# HVIB_v2.net
KiCad netlist of a schematic drawn in EAGLE
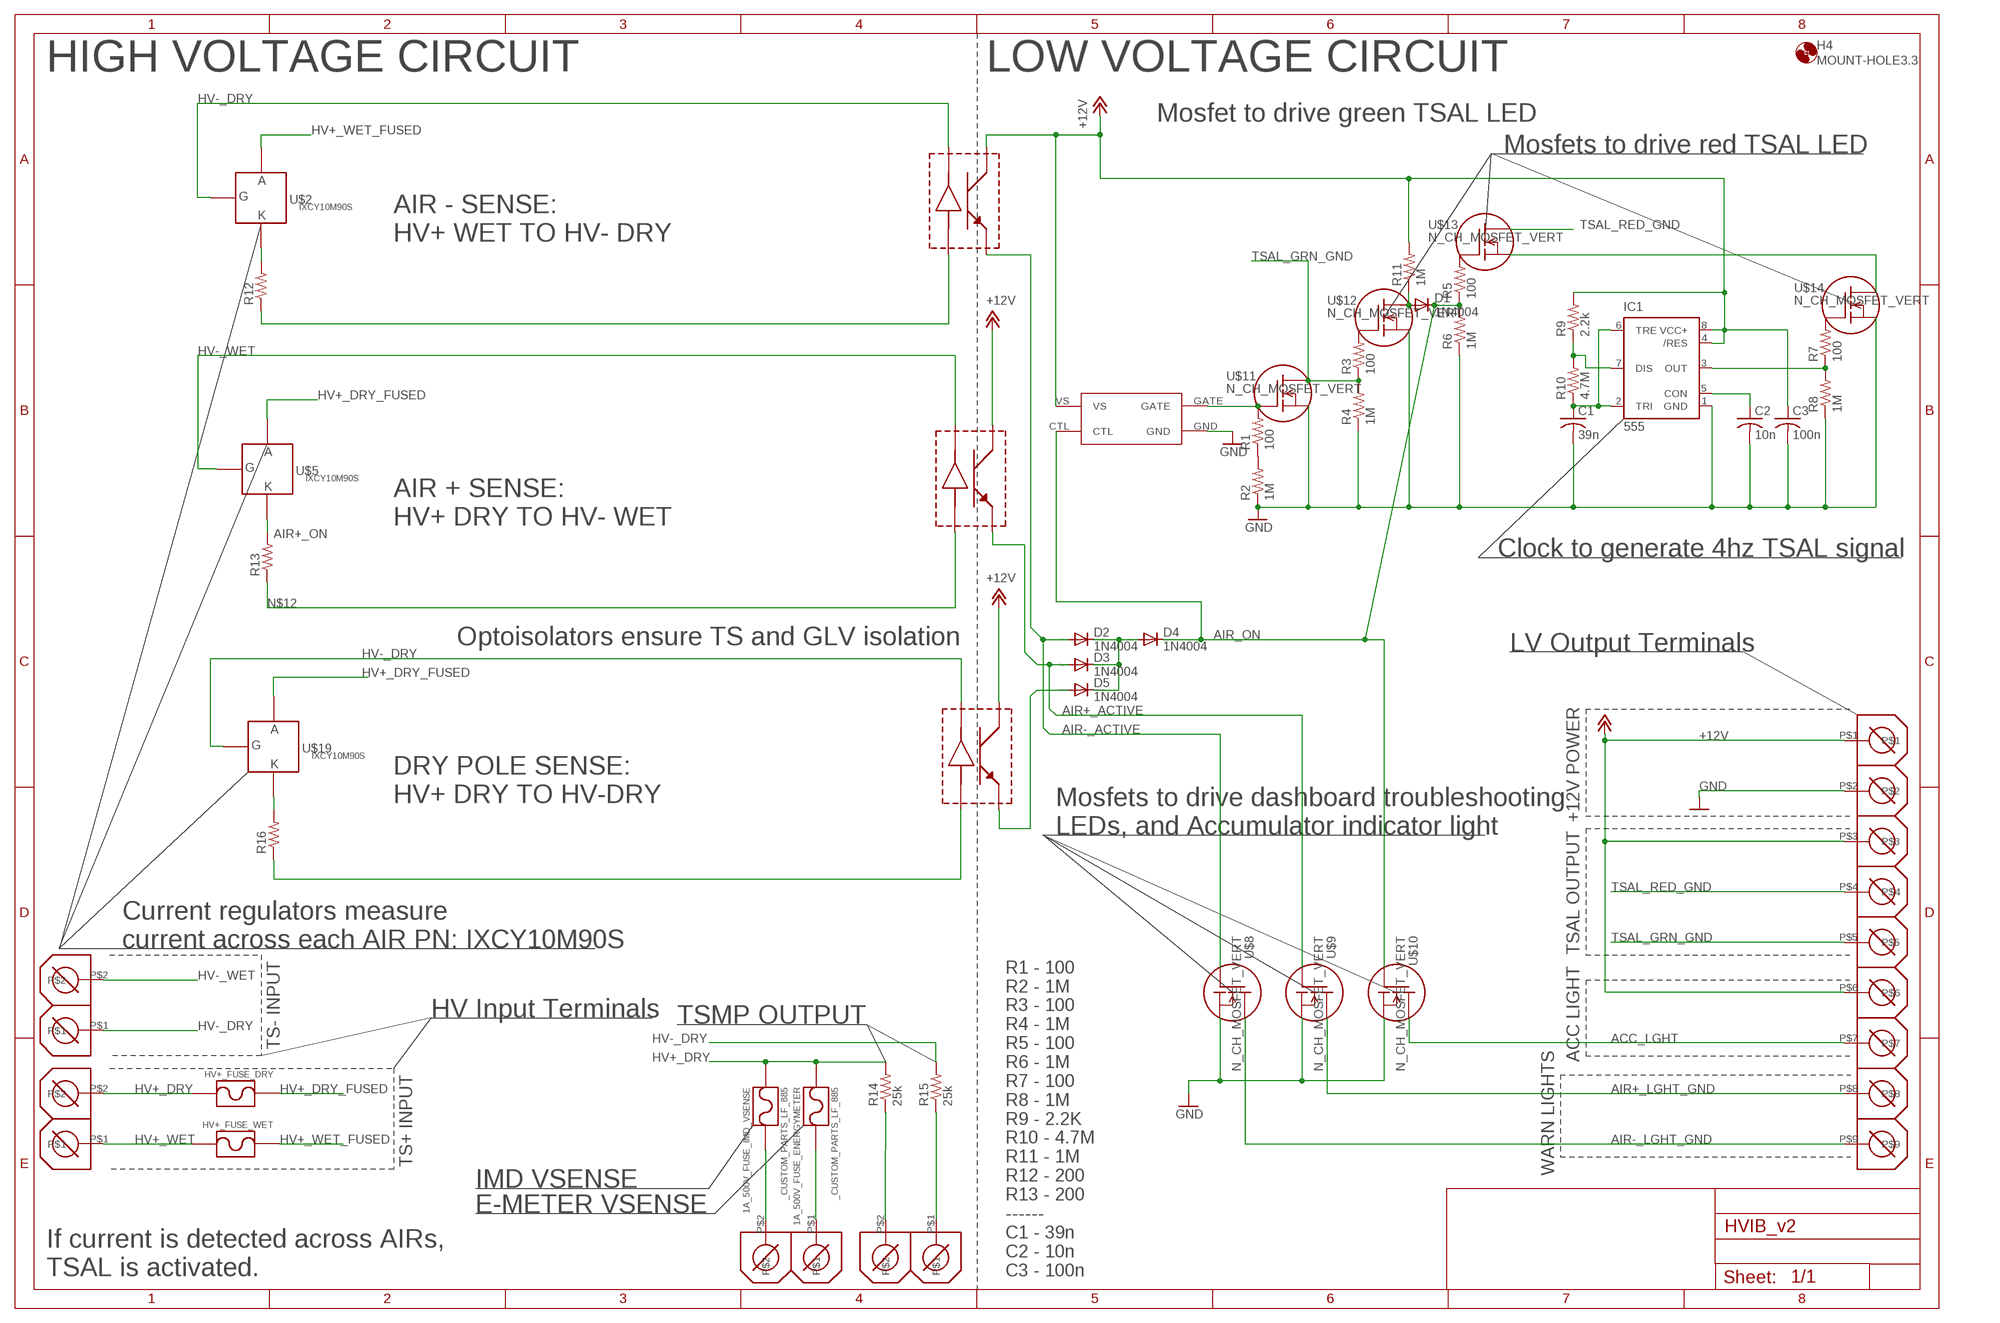
[diagram p0: schematic, sheet 1]

(export (version "E")
  (design (tool "Eeschema 10.0.6"))
  (components
    (comp (ref "1A_500V_FUSE_ENERGYMETER")
      (value "_CUSTOM_PARTS_LF_885")
      (footprint "eagle-import:_CUSTOM_PARTS_LF_885")
      (libsource (lib "eagle-import") (part "_CUSTOM_PARTS_LF_885"))
    )
    (comp (ref "1A_500V_FUSE_IMD_VSENSE")
      (value "_CUSTOM_PARTS_LF_885")
      (footprint "eagle-import:_CUSTOM_PARTS_LF_885")
      (libsource (lib "eagle-import") (part "_CUSTOM_PARTS_LF_885"))
    )
    (comp (ref "C1")
      (value "39n")
      (footprint "eagle-import:C025-024X044")
      (libsource (lib "eagle-import") (part "C-US025-024X044"))
    )
    (comp (ref "C2")
      (value "10n")
      (footprint "eagle-import:C025-024X044")
      (libsource (lib "eagle-import") (part "C-US025-024X044"))
    )
    (comp (ref "C3")
      (value "100n")
      (footprint "eagle-import:C0603")
      (libsource (lib "eagle-import") (part "C-USC0603"))
    )
    (comp (ref "D1")
      (value "1N4004")
      (footprint "eagle-import:DO41-10")
      (libsource (lib "eagle-import") (part "1N4004"))
    )
    (comp (ref "D2")
      (value "1N4004")
      (footprint "eagle-import:DO41-10")
      (libsource (lib "eagle-import") (part "1N4004"))
    )
    (comp (ref "D3")
      (value "1N4004")
      (footprint "eagle-import:DO41-10")
      (libsource (lib "eagle-import") (part "1N4004"))
    )
    (comp (ref "D4")
      (value "1N4004")
      (footprint "eagle-import:DO41-10")
      (libsource (lib "eagle-import") (part "1N4004"))
    )
    (comp (ref "D5")
      (value "1N4004")
      (footprint "eagle-import:DO41-10")
      (libsource (lib "eagle-import") (part "1N4004"))
    )
    (comp (ref "H4")
      (value "MOUNT-HOLE3.3")
      (footprint "eagle-import:3,3")
      (libsource (lib "eagle-import") (part "MOUNT-HOLE3.3"))
    )
    (comp (ref "HV+_FUSE_DRY")
      (value "_CUSTOM_PARTS_LF_885")
      (footprint "eagle-import:_CUSTOM_PARTS_LF_885")
      (libsource (lib "eagle-import") (part "_CUSTOM_PARTS_LF_885"))
    )
    (comp (ref "HV+_FUSE_WET")
      (value "_CUSTOM_PARTS_LF_885")
      (footprint "eagle-import:_CUSTOM_PARTS_LF_885")
      (libsource (lib "eagle-import") (part "_CUSTOM_PARTS_LF_885"))
    )
    (comp (ref "IC1")
      (value "555")
      (footprint "eagle-import:DIP08")
      (libsource (lib "eagle-import") (part "555P"))
    )
    (comp (ref "R1")
      (value "100")
      (footprint "eagle-import:0204_5")
      (libsource (lib "eagle-import") (part "R-US_0204/5"))
    )
    (comp (ref "R2")
      (value "1M")
      (footprint "eagle-import:0204_5")
      (libsource (lib "eagle-import") (part "R-US_0204/5"))
    )
    (comp (ref "R3")
      (value "100")
      (footprint "eagle-import:0204_5")
      (libsource (lib "eagle-import") (part "R-US_0204/5"))
    )
    (comp (ref "R4")
      (value "1M")
      (footprint "eagle-import:0204_5")
      (libsource (lib "eagle-import") (part "R-US_0204/5"))
    )
    (comp (ref "R5")
      (value "100")
      (footprint "eagle-import:0204_5")
      (libsource (lib "eagle-import") (part "R-US_0204/5"))
    )
    (comp (ref "R6")
      (value "1M")
      (footprint "eagle-import:0204_5")
      (libsource (lib "eagle-import") (part "R-US_0204/5"))
    )
    (comp (ref "R7")
      (value "100")
      (footprint "eagle-import:0204_5")
      (libsource (lib "eagle-import") (part "R-US_0204/5"))
    )
    (comp (ref "R8")
      (value "1M")
      (footprint "eagle-import:0204_5")
      (libsource (lib "eagle-import") (part "R-US_0204/5"))
    )
    (comp (ref "R9")
      (value "2.2k")
      (footprint "eagle-import:0204_5")
      (libsource (lib "eagle-import") (part "R-US_0204/5"))
    )
    (comp (ref "R10")
      (value "4.7M")
      (footprint "eagle-import:0204_5")
      (libsource (lib "eagle-import") (part "R-US_0204/5"))
    )
    (comp (ref "R11")
      (value "1M")
      (footprint "eagle-import:0204_5")
      (libsource (lib "eagle-import") (part "R-US_0204/5"))
    )
    (comp (ref "R12")
      (value "R-US_R2010")
      (footprint "eagle-import:R2010")
      (libsource (lib "eagle-import") (part "R-US_R2010"))
    )
    (comp (ref "R13")
      (value "R-US_R2010")
      (footprint "eagle-import:R2010")
      (libsource (lib "eagle-import") (part "R-US_R2010"))
    )
    (comp (ref "R14")
      (value "25k")
      (footprint "eagle-import:R2010")
      (libsource (lib "eagle-import") (part "R-US_R2010"))
    )
    (comp (ref "R15")
      (value "25k")
      (footprint "eagle-import:R2010")
      (libsource (lib "eagle-import") (part "R-US_R2010"))
    )
    (comp (ref "R16")
      (value "R-US_R2010")
      (footprint "eagle-import:R2010")
      (libsource (lib "eagle-import") (part "R-US_R2010"))
    )
    (comp (ref "U$1")
      (value "OPI7002")
      (footprint "eagle-import:DIL04")
      (libsource (lib "eagle-import") (part "OPI7002"))
    )
    (comp (ref "U$2")
      (value "IXCY10M90S")
      (footprint "eagle-import:D2PACK")
      (libsource (lib "eagle-import") (part "IXCY10M90S"))
    )
    (comp (ref "U$3")
      (value "OPI7002")
      (footprint "eagle-import:DIL04")
      (libsource (lib "eagle-import") (part "OPI7002"))
    )
    (comp (ref "U$4")
      (value "DCDC_PARTS_282838-2_TE")
      (footprint "eagle-import:DCDC_PARTS_282838-2_FOOT")
      (libsource (lib "eagle-import") (part "DCDC_PARTS_282838-2_TE"))
    )
    (comp (ref "U$5")
      (value "IXCY10M90S")
      (footprint "eagle-import:D2PACK")
      (libsource (lib "eagle-import") (part "IXCY10M90S"))
    )
    (comp (ref "U$6")
      (value "DCDC_PARTS_282838-2_TE")
      (footprint "eagle-import:DCDC_PARTS_282838-2_FOOT")
      (libsource (lib "eagle-import") (part "DCDC_PARTS_282838-2_TE"))
    )
    (comp (ref "U$7")
      (value "PHOENIX_1725724")
      (footprint "eagle-import:1725724_FOOT")
      (libsource (lib "eagle-import") (part "PHOENIX_1725724"))
    )
    (comp (ref "U$8")
      (value "N_CH_MOSFET_VERT")
      (footprint "eagle-import:TO220V")
      (libsource (lib "eagle-import") (part "N_CH_MOSFET_VERT"))
    )
    (comp (ref "U$9")
      (value "N_CH_MOSFET_VERT")
      (footprint "eagle-import:TO220V")
      (libsource (lib "eagle-import") (part "N_CH_MOSFET_VERT"))
    )
    (comp (ref "U$10")
      (value "N_CH_MOSFET_VERT")
      (footprint "eagle-import:TO220V")
      (libsource (lib "eagle-import") (part "N_CH_MOSFET_VERT"))
    )
    (comp (ref "U$11")
      (value "N_CH_MOSFET_VERT")
      (footprint "eagle-import:TO220V")
      (libsource (lib "eagle-import") (part "N_CH_MOSFET_VERT"))
    )
    (comp (ref "U$12")
      (value "N_CH_MOSFET_VERT")
      (footprint "eagle-import:TO220V")
      (libsource (lib "eagle-import") (part "N_CH_MOSFET_VERT"))
    )
    (comp (ref "U$13")
      (value "N_CH_MOSFET_VERT")
      (footprint "eagle-import:TO220V")
      (libsource (lib "eagle-import") (part "N_CH_MOSFET_VERT"))
    )
    (comp (ref "U$14")
      (value "N_CH_MOSFET_VERT")
      (footprint "eagle-import:TO220V")
      (libsource (lib "eagle-import") (part "N_CH_MOSFET_VERT"))
    )
    (comp (ref "U$15")
      (value "MIC4417")
      (footprint "eagle-import:PDM_2019_REVB_MIC4416YM4-TR")
      (libsource (lib "eagle-import") (part "MIC4417"))
    )
    (comp (ref "U$16")
      (value "DCDC_PARTS_282838-2_TE")
      (footprint "eagle-import:DCDC_PARTS_282838-2_FOOT")
      (libsource (lib "eagle-import") (part "DCDC_PARTS_282838-2_TE"))
    )
    (comp (ref "U$17")
      (value "DCDC_PARTS_282838-2_TE")
      (footprint "eagle-import:DCDC_PARTS_282838-2_FOOT")
      (libsource (lib "eagle-import") (part "DCDC_PARTS_282838-2_TE"))
    )
    (comp (ref "U$18")
      (value "OPI7002")
      (footprint "eagle-import:DIL04")
      (libsource (lib "eagle-import") (part "OPI7002"))
    )
    (comp (ref "U$19")
      (value "IXCY10M90S")
      (footprint "eagle-import:D2PACK")
      (libsource (lib "eagle-import") (part "IXCY10M90S"))
    )
  )
  (nets
    (net (code "1") (name "+12V") (class "Default")
      (node (ref "C3") (pin "1") (pinfunction "1_1") (pintype "passive"))
      (node (ref "IC1") (pin "4") (pinfunction "/RES_4") (pintype "input"))
      (node (ref "IC1") (pin "8") (pinfunction "VCC+_8") (pintype "power_in"))
      (node (ref "R11") (pin "2") (pinfunction "2_2") (pintype "passive"))
      (node (ref "R9") (pin "2") (pinfunction "2_2") (pintype "passive"))
      (node (ref "U$1") (pin "3") (pinfunction "COLLECTOR_3") (pintype "bidirectional"))
      (node (ref "U$15") (pin "VS") (pinfunction "VS_VS") (pintype "bidirectional"))
      (node (ref "U$18") (pin "3") (pinfunction "COLLECTOR_3") (pintype "bidirectional"))
      (node (ref "U$3") (pin "3") (pinfunction "COLLECTOR_3") (pintype "bidirectional"))
      (node (ref "U$7") (pin "P$1") (pinfunction "P$1_P$1") (pintype "bidirectional"))
      (node (ref "U$7") (pin "P$3") (pinfunction "P$3_P$3") (pintype "bidirectional"))
      (node (ref "U$7") (pin "P$6") (pinfunction "P$6_P$6") (pintype "bidirectional"))
    )
    (net (code "2") (name "/ACC_LGHT") (class "Default")
      (node (ref "U$10") (pin "2") (pinfunction "D_2") (pintype "passive"))
      (node (ref "U$7") (pin "P$7") (pinfunction "P$7_P$7") (pintype "bidirectional"))
    )
    (net (code "3") (name "/AIR+_ACTIVE") (class "Default")
      (node (ref "D3") (pin "A") (pinfunction "A_A") (pintype "passive"))
      (node (ref "U$1") (pin "4") (pinfunction "EMITTER_4") (pintype "bidirectional"))
      (node (ref "U$9") (pin "1") (pinfunction "G_1") (pintype "passive"))
    )
    (net (code "4") (name "/AIR+_LGHT_GND") (class "Default")
      (node (ref "U$7") (pin "P$8") (pinfunction "P$8_P$8") (pintype "bidirectional"))
      (node (ref "U$9") (pin "2") (pinfunction "D_2") (pintype "passive"))
    )
    (net (code "5") (name "/AIR+_ON") (class "Default")
      (node (ref "R13") (pin "2") (pinfunction "2_2") (pintype "passive"))
      (node (ref "U$5") (pin "3") (pinfunction "K_3") (pintype "bidirectional"))
    )
    (net (code "6") (name "/AIR-_ACTIVE") (class "Default")
      (node (ref "D2") (pin "A") (pinfunction "A_A") (pintype "passive"))
      (node (ref "U$3") (pin "4") (pinfunction "EMITTER_4") (pintype "bidirectional"))
      (node (ref "U$8") (pin "1") (pinfunction "G_1") (pintype "passive"))
    )
    (net (code "7") (name "/AIR-_LGHT_GND") (class "Default")
      (node (ref "U$7") (pin "P$9") (pinfunction "P$9_P$9") (pintype "bidirectional"))
      (node (ref "U$8") (pin "2") (pinfunction "D_2") (pintype "passive"))
    )
    (net (code "8") (name "/AIR_ON") (class "Default")
      (node (ref "D1") (pin "C") (pinfunction "C_C") (pintype "passive"))
      (node (ref "D4") (pin "C") (pinfunction "C_C") (pintype "passive"))
      (node (ref "R5") (pin "1") (pinfunction "1_1") (pintype "passive"))
      (node (ref "R6") (pin "2") (pinfunction "2_2") (pintype "passive"))
      (node (ref "U$10") (pin "1") (pinfunction "G_1") (pintype "passive"))
      (node (ref "U$15") (pin "CTL") (pinfunction "CTL_CTL") (pintype "bidirectional"))
    )
    (net (code "9") (name "/HV+_DRY") (class "Default")
      (node (ref "1A_500V_FUSE_ENERGYMETER") (pin "P$1") (pinfunction "P$1_P$1") (pintype "bidirectional"))
      (node (ref "1A_500V_FUSE_IMD_VSENSE") (pin "P$1") (pinfunction "P$1_P$1") (pintype "bidirectional"))
      (node (ref "HV+_FUSE_DRY") (pin "P$2") (pinfunction "P$2_P$2") (pintype "bidirectional"))
      (node (ref "R14") (pin "2") (pinfunction "2_2") (pintype "passive"))
      (node (ref "U$6") (pin "P$2") (pinfunction "P$2_P$2") (pintype "bidirectional"))
    )
    (net (code "10") (name "/HV+_DRY_FUSED") (class "Default")
      (node (ref "HV+_FUSE_DRY") (pin "P$1") (pinfunction "P$1_P$1") (pintype "bidirectional"))
      (node (ref "U$19") (pin "2") (pinfunction "A_2") (pintype "bidirectional"))
      (node (ref "U$5") (pin "2") (pinfunction "A_2") (pintype "bidirectional"))
    )
    (net (code "11") (name "/HV+_WET") (class "Default")
      (node (ref "HV+_FUSE_WET") (pin "P$2") (pinfunction "P$2_P$2") (pintype "bidirectional"))
      (node (ref "U$6") (pin "P$1") (pinfunction "P$1_P$1") (pintype "bidirectional"))
    )
    (net (code "12") (name "/HV+_WET_FUSED") (class "Default")
      (node (ref "HV+_FUSE_WET") (pin "P$1") (pinfunction "P$1_P$1") (pintype "bidirectional"))
      (node (ref "U$2") (pin "2") (pinfunction "A_2") (pintype "bidirectional"))
    )
    (net (code "13") (name "/HV-_DRY") (class "Default")
      (node (ref "R15") (pin "2") (pinfunction "2_2") (pintype "passive"))
      (node (ref "U$18") (pin "2") (pinfunction "CATHODE_2") (pintype "bidirectional"))
      (node (ref "U$19") (pin "1") (pinfunction "G_1") (pintype "bidirectional"))
      (node (ref "U$2") (pin "1") (pinfunction "G_1") (pintype "bidirectional"))
      (node (ref "U$3") (pin "2") (pinfunction "CATHODE_2") (pintype "bidirectional"))
      (node (ref "U$4") (pin "P$1") (pinfunction "P$1_P$1") (pintype "bidirectional"))
    )
    (net (code "14") (name "/HV-_WET") (class "Default")
      (node (ref "U$1") (pin "2") (pinfunction "CATHODE_2") (pintype "bidirectional"))
      (node (ref "U$4") (pin "P$2") (pinfunction "P$2_P$2") (pintype "bidirectional"))
      (node (ref "U$5") (pin "1") (pinfunction "G_1") (pintype "bidirectional"))
    )
    (net (code "15") (name "/N$12") (class "Default")
      (node (ref "R13") (pin "1") (pinfunction "1_1") (pintype "passive"))
      (node (ref "U$1") (pin "1") (pinfunction "ANODE_1") (pintype "bidirectional"))
    )
    (net (code "16") (name "/TSAL_GRN_GND") (class "Default")
      (node (ref "R3") (pin "1") (pinfunction "1_1") (pintype "passive"))
      (node (ref "R4") (pin "2") (pinfunction "2_2") (pintype "passive"))
      (node (ref "U$11") (pin "2") (pinfunction "D_2") (pintype "passive"))
      (node (ref "U$7") (pin "P$5") (pinfunction "P$5_P$5") (pintype "bidirectional"))
    )
    (net (code "17") (name "/TSAL_RED_GND") (class "Default")
      (node (ref "U$13") (pin "2") (pinfunction "D_2") (pintype "passive"))
      (node (ref "U$7") (pin "P$4") (pinfunction "P$4_P$4") (pintype "bidirectional"))
    )
    (net (code "18") (name "GND") (class "Default")
      (node (ref "C1") (pin "2") (pinfunction "2_2") (pintype "passive"))
      (node (ref "C2") (pin "2") (pinfunction "2_2") (pintype "passive"))
      (node (ref "C3") (pin "2") (pinfunction "2_2") (pintype "passive"))
      (node (ref "IC1") (pin "1") (pinfunction "GND_1") (pintype "power_in"))
      (node (ref "R2") (pin "1") (pinfunction "1_1") (pintype "passive"))
      (node (ref "R4") (pin "1") (pinfunction "1_1") (pintype "passive"))
      (node (ref "R6") (pin "1") (pinfunction "1_1") (pintype "passive"))
      (node (ref "R8") (pin "1") (pinfunction "1_1") (pintype "passive"))
      (node (ref "U$10") (pin "3") (pinfunction "S_3") (pintype "passive"))
      (node (ref "U$11") (pin "3") (pinfunction "S_3") (pintype "passive"))
      (node (ref "U$12") (pin "3") (pinfunction "S_3") (pintype "passive"))
      (node (ref "U$14") (pin "3") (pinfunction "S_3") (pintype "passive"))
      (node (ref "U$15") (pin "GND") (pinfunction "GND_GND") (pintype "bidirectional"))
      (node (ref "U$7") (pin "P$2") (pinfunction "P$2_P$2") (pintype "bidirectional"))
      (node (ref "U$8") (pin "3") (pinfunction "S_3") (pintype "passive"))
      (node (ref "U$9") (pin "3") (pinfunction "S_3") (pintype "passive"))
    )
    (net (code "19") (name "Net-(1A_500V_FUSE_ENERGYMETER-PadP$2)") (class "Default")
      (node (ref "1A_500V_FUSE_ENERGYMETER") (pin "P$2") (pinfunction "P$2_P$2") (pintype "bidirectional"))
      (node (ref "U$17") (pin "P$1") (pinfunction "P$1_P$1") (pintype "bidirectional"))
    )
    (net (code "20") (name "Net-(1A_500V_FUSE_IMD_VSENSE-PadP$2)") (class "Default")
      (node (ref "1A_500V_FUSE_IMD_VSENSE") (pin "P$2") (pinfunction "P$2_P$2") (pintype "bidirectional"))
      (node (ref "U$17") (pin "P$2") (pinfunction "P$2_P$2") (pintype "bidirectional"))
    )
    (net (code "21") (name "Net-(D2-PadC)") (class "Default")
      (node (ref "D2") (pin "C") (pinfunction "C_C") (pintype "passive"))
      (node (ref "D3") (pin "C") (pinfunction "C_C") (pintype "passive"))
      (node (ref "D4") (pin "A") (pinfunction "A_A") (pintype "passive"))
      (node (ref "D5") (pin "C") (pinfunction "C_C") (pintype "passive"))
    )
    (net (code "22") (name "Net-(IC1-CON)") (class "Default")
      (node (ref "C2") (pin "1") (pinfunction "1_1") (pintype "passive"))
      (node (ref "IC1") (pin "5") (pinfunction "CON_5") (pintype "input"))
    )
    (net (code "23") (name "Net-(IC1-DIS)") (class "Default")
      (node (ref "IC1") (pin "7") (pinfunction "DIS_7") (pintype "input"))
      (node (ref "R10") (pin "2") (pinfunction "2_2") (pintype "passive"))
      (node (ref "R9") (pin "1") (pinfunction "1_1") (pintype "passive"))
    )
    (net (code "24") (name "Net-(IC1-OUT)") (class "Default")
      (node (ref "IC1") (pin "3") (pinfunction "OUT_3") (pintype "output"))
      (node (ref "R7") (pin "1") (pinfunction "1_1") (pintype "passive"))
      (node (ref "R8") (pin "2") (pinfunction "2_2") (pintype "passive"))
    )
    (net (code "25") (name "Net-(IC1-TRE)") (class "Default")
      (node (ref "C1") (pin "1") (pinfunction "1_1") (pintype "passive"))
      (node (ref "IC1") (pin "2") (pinfunction "TRI_2") (pintype "input"))
      (node (ref "IC1") (pin "6") (pinfunction "TRE_6") (pintype "input"))
      (node (ref "R10") (pin "1") (pinfunction "1_1") (pintype "passive"))
    )
    (net (code "26") (name "Net-(R1-Pad1)") (class "Default")
      (node (ref "R1") (pin "1") (pinfunction "1_1") (pintype "passive"))
      (node (ref "R2") (pin "2") (pinfunction "2_2") (pintype "passive"))
    )
    (net (code "27") (name "Net-(R14-Pad1)") (class "Default")
      (node (ref "R14") (pin "1") (pinfunction "1_1") (pintype "passive"))
      (node (ref "U$16") (pin "P$2") (pinfunction "P$2_P$2") (pintype "bidirectional"))
    )
    (net (code "28") (name "Net-(R15-Pad1)") (class "Default")
      (node (ref "R15") (pin "1") (pinfunction "1_1") (pintype "passive"))
      (node (ref "U$16") (pin "P$1") (pinfunction "P$1_P$1") (pintype "bidirectional"))
    )
    (net (code "29") (name "Net-(U$2-K)") (class "Default")
      (node (ref "R12") (pin "2") (pinfunction "2_2") (pintype "passive"))
      (node (ref "U$2") (pin "3") (pinfunction "K_3") (pintype "bidirectional"))
    )
    (net (code "30") (name "Net-(U$3-ANODE)") (class "Default")
      (node (ref "R12") (pin "1") (pinfunction "1_1") (pintype "passive"))
      (node (ref "U$3") (pin "1") (pinfunction "ANODE_1") (pintype "bidirectional"))
    )
    (net (code "31") (name "Net-(U$11-G)") (class "Default")
      (node (ref "R1") (pin "2") (pinfunction "2_2") (pintype "passive"))
      (node (ref "U$11") (pin "1") (pinfunction "G_1") (pintype "passive"))
      (node (ref "U$15") (pin "GATE") (pinfunction "GATE_GATE") (pintype "bidirectional"))
    )
    (net (code "32") (name "Net-(U$12-D)") (class "Default")
      (node (ref "D1") (pin "A") (pinfunction "A_A") (pintype "passive"))
      (node (ref "R11") (pin "1") (pinfunction "1_1") (pintype "passive"))
      (node (ref "U$12") (pin "2") (pinfunction "D_2") (pintype "passive"))
    )
    (net (code "33") (name "Net-(U$12-G)") (class "Default")
      (node (ref "R3") (pin "2") (pinfunction "2_2") (pintype "passive"))
      (node (ref "U$12") (pin "1") (pinfunction "G_1") (pintype "passive"))
    )
    (net (code "34") (name "Net-(U$13-G)") (class "Default")
      (node (ref "R5") (pin "2") (pinfunction "2_2") (pintype "passive"))
      (node (ref "U$13") (pin "1") (pinfunction "G_1") (pintype "passive"))
    )
    (net (code "35") (name "Net-(U$13-S)") (class "Default")
      (node (ref "U$13") (pin "3") (pinfunction "S_3") (pintype "passive"))
      (node (ref "U$14") (pin "2") (pinfunction "D_2") (pintype "passive"))
    )
    (net (code "36") (name "Net-(U$14-G)") (class "Default")
      (node (ref "R7") (pin "2") (pinfunction "2_2") (pintype "passive"))
      (node (ref "U$14") (pin "1") (pinfunction "G_1") (pintype "passive"))
    )
    (net (code "37") (name "Net-(U$18-ANODE)") (class "Default")
      (node (ref "R16") (pin "1") (pinfunction "1_1") (pintype "passive"))
      (node (ref "U$18") (pin "1") (pinfunction "ANODE_1") (pintype "bidirectional"))
    )
    (net (code "38") (name "Net-(U$18-EMITTER)") (class "Default")
      (node (ref "D5") (pin "A") (pinfunction "A_A") (pintype "passive"))
      (node (ref "U$18") (pin "4") (pinfunction "EMITTER_4") (pintype "bidirectional"))
    )
    (net (code "39") (name "Net-(U$19-K)") (class "Default")
      (node (ref "R16") (pin "2") (pinfunction "2_2") (pintype "passive"))
      (node (ref "U$19") (pin "3") (pinfunction "K_3") (pintype "bidirectional"))
    )
  )
)
